# MainCon.net
KiCad netlist of a schematic drawn in Altium Designer
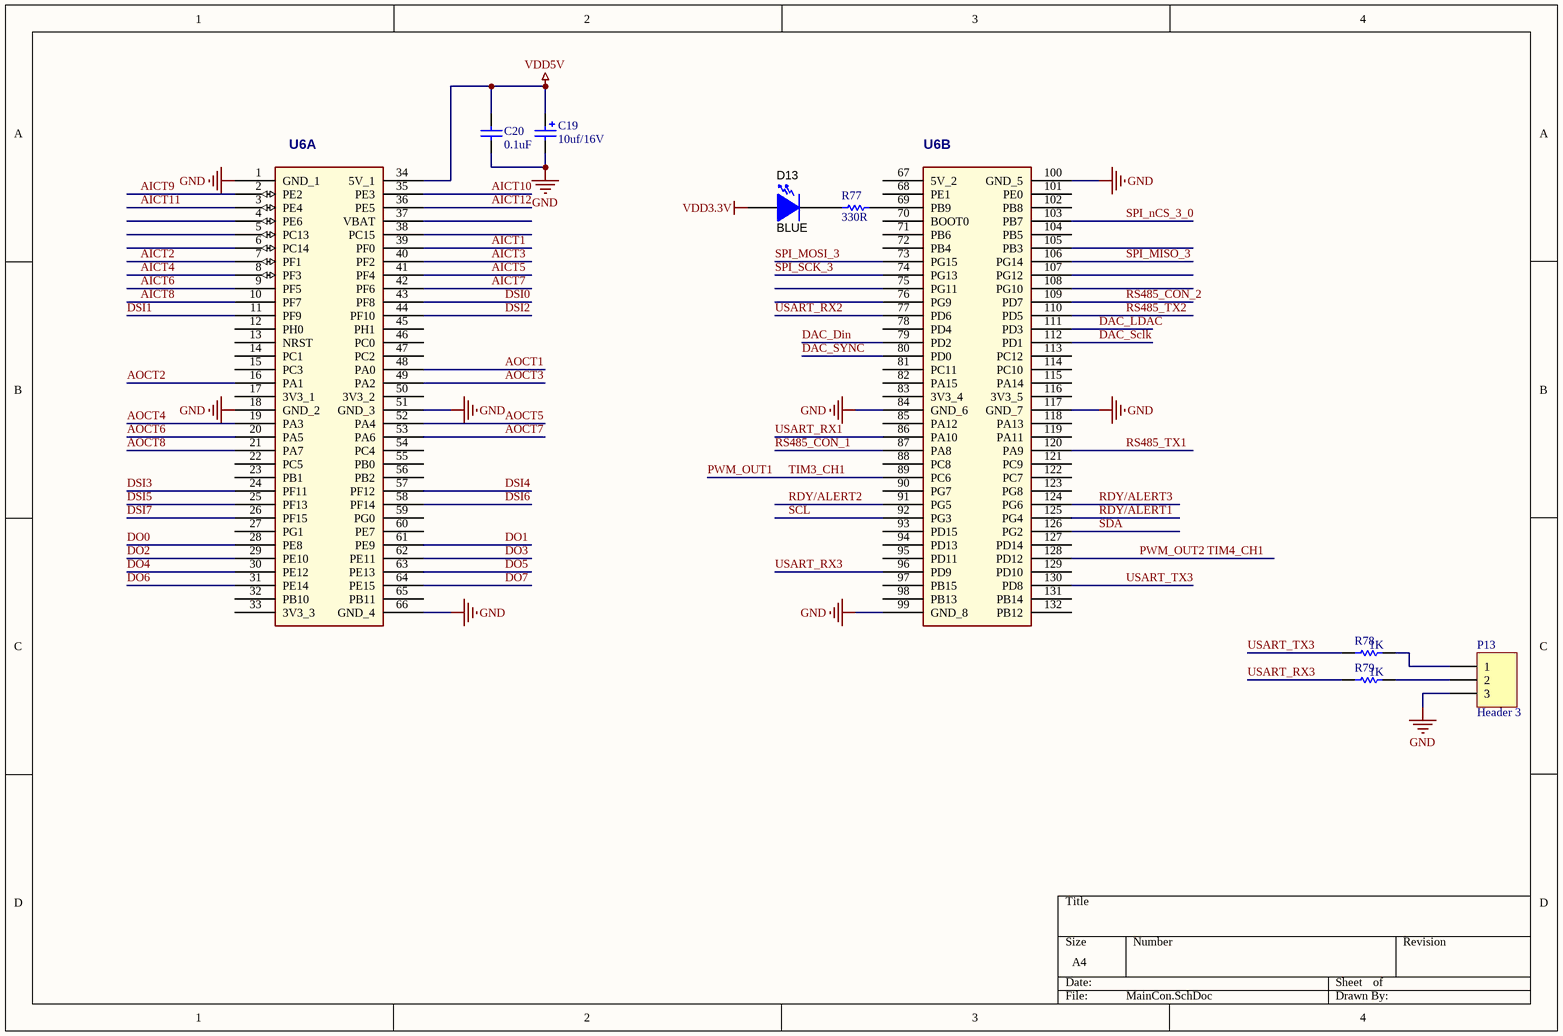
[diagram p0: MainCon.SchDoc]

(export (version "E")
  (design (tool "Eeschema 10.0.6"))
  (components
    (comp (ref "C19")
      (value "10uf/16V")
      (footprint "Cap-A")
      (description "Polarized Capacitor (Axial)")
      (fields (field (name "PUBLISHER") "Altium Limited"))
      (libsource (lib "Miscellaneous Devices") (part "Cap Pol2"))
    )
    (comp (ref "C20")
      (value "0.1uF")
      (footprint "C0805")
      (description "Capacitor")
      (fields (field (name "Comment") "Cap") (field (name "PUBLISHER") "Altium Limited"))
      (libsource (lib "main board") (part "Cap_2"))
    )
    (comp (ref "D13")
      (value "BLUE")
      (footprint "D0805")
      (description "LED, GREEN SMD")
      (fields
        (field (name "MANUFACTURER") "Rohm")
        (field (name "PARTNUMBER") "SML-P12YTT86")
        (field (name "PUBLISHER") "Texas Instruments")
      )
      (libsource (lib "REl") (part "SML-P12YTT86"))
    )
    (comp (ref "P13")
      (value "Header 3")
      (footprint "HDR1X3")
      (description "Header, 3-Pin")
      (fields (field (name "PUBLISHER") "Altium Limited"))
      (libsource (lib "Miscellaneous Connectors") (part "Header 3"))
    )
    (comp (ref "R77")
      (value "330R")
      (footprint "0805")
      (description "Semiconductor Resistor")
      (fields (field (name "Comment") "Res Semi") (field (name "PUBLISHER") "Altium Limited"))
      (libsource (lib "Miscellaneous Devices") (part "Res Semi"))
    )
    (comp (ref "R78")
      (value "1K")
      (footprint "0805")
      (description "Resistor")
      (fields (field (name "Comment") "Res1") (field (name "PUBLISHER") "Altium Limited"))
      (libsource (lib "Miscellaneous Devices") (part "Res1"))
    )
    (comp (ref "R79")
      (value "1K")
      (footprint "0805")
      (description "Resistor")
      (fields (field (name "Comment") "Res1") (field (name "PUBLISHER") "Altium Limited"))
      (libsource (lib "Miscellaneous Devices") (part "Res1"))
    )
    (comp (ref "U6") (value "STM32Z_MOD") (libsource (lib "*") (part "STM32Z_MOD")))
  )
  (nets
    (net (code "1") (name "/AICT1") (class "Default")
      (node (ref "U6") (pin "39") (pinfunction "PF0_39") (pintype "passive"))
    )
    (net (code "2") (name "/AICT2") (class "Default")
      (node (ref "U6") (pin "7") (pinfunction "PF1_7") (pintype "bidirectional"))
    )
    (net (code "3") (name "/AICT3") (class "Default")
      (node (ref "U6") (pin "40") (pinfunction "PF2_40") (pintype "passive"))
    )
    (net (code "4") (name "/AICT4") (class "Default")
      (node (ref "U6") (pin "8") (pinfunction "PF3_8") (pintype "bidirectional"))
    )
    (net (code "5") (name "/AICT5") (class "Default")
      (node (ref "U6") (pin "41") (pinfunction "PF4_41") (pintype "passive"))
    )
    (net (code "6") (name "/AICT6") (class "Default")
      (node (ref "U6") (pin "9") (pinfunction "PF5_9") (pintype "passive"))
    )
    (net (code "7") (name "/AICT7") (class "Default")
      (node (ref "U6") (pin "42") (pinfunction "PF6_42") (pintype "passive"))
    )
    (net (code "8") (name "/AICT8") (class "Default")
      (node (ref "U6") (pin "10") (pinfunction "PF7_10") (pintype "passive"))
    )
    (net (code "9") (name "/AICT9") (class "Default")
      (node (ref "U6") (pin "2") (pinfunction "PE2_2") (pintype "bidirectional"))
    )
    (net (code "10") (name "/AICT10") (class "Default")
      (node (ref "U6") (pin "35") (pinfunction "PE3_35") (pintype "passive"))
    )
    (net (code "11") (name "/AICT11") (class "Default")
      (node (ref "U6") (pin "3") (pinfunction "PE4_3") (pintype "bidirectional"))
    )
    (net (code "12") (name "/AICT12") (class "Default")
      (node (ref "U6") (pin "36") (pinfunction "PE5_36") (pintype "passive"))
    )
    (net (code "13") (name "/AOCT1") (class "Default")
      (node (ref "U6") (pin "48") (pinfunction "PA0_48") (pintype "passive"))
    )
    (net (code "14") (name "/AOCT2") (class "Default")
      (node (ref "U6") (pin "16") (pinfunction "PA1_16") (pintype "passive"))
    )
    (net (code "15") (name "/AOCT3") (class "Default")
      (node (ref "U6") (pin "49") (pinfunction "PA2_49") (pintype "passive"))
    )
    (net (code "16") (name "/AOCT4") (class "Default")
      (node (ref "U6") (pin "19") (pinfunction "PA3_19") (pintype "passive"))
    )
    (net (code "17") (name "/AOCT5") (class "Default")
      (node (ref "U6") (pin "52") (pinfunction "PA4_52") (pintype "passive"))
    )
    (net (code "18") (name "/AOCT6") (class "Default")
      (node (ref "U6") (pin "20") (pinfunction "PA5_20") (pintype "passive"))
    )
    (net (code "19") (name "/AOCT7") (class "Default")
      (node (ref "U6") (pin "53") (pinfunction "PA6_53") (pintype "passive"))
    )
    (net (code "20") (name "/AOCT8") (class "Default")
      (node (ref "U6") (pin "21") (pinfunction "PA7_21") (pintype "passive"))
    )
    (net (code "21") (name "/DAC_Din") (class "Default")
      (node (ref "U6") (pin "79") (pinfunction "PD2_79") (pintype "passive"))
    )
    (net (code "22") (name "/DAC_LDAC") (class "Default")
      (node (ref "U6") (pin "111") (pinfunction "PD3_111") (pintype "passive"))
    )
    (net (code "23") (name "/DAC_SYNC") (class "Default")
      (node (ref "U6") (pin "80") (pinfunction "PD0_80") (pintype "passive"))
    )
    (net (code "24") (name "/DAC_Sclk") (class "Default")
      (node (ref "U6") (pin "112") (pinfunction "PD1_112") (pintype "passive"))
    )
    (net (code "25") (name "/DO0") (class "Default")
      (node (ref "U6") (pin "28") (pinfunction "PE8_28") (pintype "passive"))
    )
    (net (code "26") (name "/DO1") (class "Default")
      (node (ref "U6") (pin "61") (pinfunction "PE9_61") (pintype "passive"))
    )
    (net (code "27") (name "/DO2") (class "Default")
      (node (ref "U6") (pin "29") (pinfunction "PE10_29") (pintype "passive"))
    )
    (net (code "28") (name "/DO3") (class "Default")
      (node (ref "U6") (pin "62") (pinfunction "PE11_62") (pintype "passive"))
    )
    (net (code "29") (name "/DO4") (class "Default")
      (node (ref "U6") (pin "30") (pinfunction "PE12_30") (pintype "passive"))
    )
    (net (code "30") (name "/DO5") (class "Default")
      (node (ref "U6") (pin "63") (pinfunction "PE13_63") (pintype "passive"))
    )
    (net (code "31") (name "/DO6") (class "Default")
      (node (ref "U6") (pin "31") (pinfunction "PE14_31") (pintype "passive"))
    )
    (net (code "32") (name "/DO7") (class "Default")
      (node (ref "U6") (pin "64") (pinfunction "PE15_64") (pintype "passive"))
    )
    (net (code "33") (name "/DSI0") (class "Default")
      (node (ref "U6") (pin "43") (pinfunction "PF8_43") (pintype "passive"))
    )
    (net (code "34") (name "/DSI1") (class "Default")
      (node (ref "U6") (pin "11") (pinfunction "PF9_11") (pintype "passive"))
    )
    (net (code "35") (name "/DSI2") (class "Default")
      (node (ref "U6") (pin "44") (pinfunction "PF10_44") (pintype "passive"))
    )
    (net (code "36") (name "/DSI3") (class "Default")
      (node (ref "U6") (pin "24") (pinfunction "PF11_24") (pintype "passive"))
    )
    (net (code "37") (name "/DSI4") (class "Default")
      (node (ref "U6") (pin "57") (pinfunction "PF12_57") (pintype "passive"))
    )
    (net (code "38") (name "/DSI5") (class "Default")
      (node (ref "U6") (pin "25") (pinfunction "PF13_25") (pintype "passive"))
    )
    (net (code "39") (name "/DSI6") (class "Default")
      (node (ref "U6") (pin "58") (pinfunction "PF14_58") (pintype "passive"))
    )
    (net (code "40") (name "/DSI7") (class "Default")
      (node (ref "U6") (pin "26") (pinfunction "PF15_26") (pintype "passive"))
    )
    (net (code "41") (name "/PWM_OUT1") (class "Default")
      (node (ref "U6") (pin "89") (pinfunction "PC6_89") (pintype "passive"))
    )
    (net (code "42") (name "/PWM_OUT2") (class "Default")
      (node (ref "U6") (pin "128") (pinfunction "PD12_128") (pintype "passive"))
    )
    (net (code "43") (name "/RDY{slash}ALERT1") (class "Default")
      (node (ref "U6") (pin "125") (pinfunction "PG4_125") (pintype "passive"))
    )
    (net (code "44") (name "/RDY{slash}ALERT2") (class "Default")
      (node (ref "U6") (pin "91") (pinfunction "PG5_91") (pintype "passive"))
    )
    (net (code "45") (name "/RDY{slash}ALERT3") (class "Default")
      (node (ref "U6") (pin "124") (pinfunction "PG6_124") (pintype "passive"))
    )
    (net (code "46") (name "/RS485_CON_1") (class "Default")
      (node (ref "U6") (pin "87") (pinfunction "PA8_87") (pintype "passive"))
    )
    (net (code "47") (name "/RS485_CON_2") (class "Default")
      (node (ref "U6") (pin "109") (pinfunction "PD7_109") (pintype "passive"))
    )
    (net (code "48") (name "/RS485_TX1") (class "Default")
      (node (ref "U6") (pin "120") (pinfunction "PA9_120") (pintype "passive"))
    )
    (net (code "49") (name "/RS485_TX2") (class "Default")
      (node (ref "U6") (pin "110") (pinfunction "PD5_110") (pintype "passive"))
    )
    (net (code "50") (name "/SCL") (class "Default")
      (node (ref "U6") (pin "92") (pinfunction "PG3_92") (pintype "passive"))
    )
    (net (code "51") (name "/SDA") (class "Default")
      (node (ref "U6") (pin "126") (pinfunction "PG2_126") (pintype "passive"))
    )
    (net (code "52") (name "/SPI_MISO_3") (class "Default")
      (node (ref "U6") (pin "106") (pinfunction "PG14_106") (pintype "passive"))
    )
    (net (code "53") (name "/SPI_MOSI_3") (class "Default")
      (node (ref "U6") (pin "73") (pinfunction "PG15_73") (pintype "passive"))
    )
    (net (code "54") (name "/SPI_SCK_3") (class "Default")
      (node (ref "U6") (pin "74") (pinfunction "PG13_74") (pintype "passive"))
    )
    (net (code "55") (name "/SPI_nCS_3_0") (class "Default")
      (node (ref "U6") (pin "103") (pinfunction "PB7_103") (pintype "passive"))
    )
    (net (code "56") (name "/USART_RX1") (class "Default")
      (node (ref "U6") (pin "86") (pinfunction "PA10_86") (pintype "passive"))
    )
    (net (code "57") (name "/USART_RX2") (class "Default")
      (node (ref "U6") (pin "77") (pinfunction "PD6_77") (pintype "passive"))
    )
    (net (code "58") (name "/USART_RX3") (class "Default")
      (node (ref "R79") (pin "1") (pinfunction "1_1") (pintype "passive"))
      (node (ref "U6") (pin "96") (pinfunction "PD9_96") (pintype "passive"))
    )
    (net (code "59") (name "/USART_TX3") (class "Default")
      (node (ref "R78") (pin "1") (pinfunction "1_1") (pintype "passive"))
      (node (ref "U6") (pin "130") (pinfunction "PD8_130") (pintype "passive"))
    )
    (net (code "60") (name "GND") (class "Default")
      (node (ref "C19") (pin "2") (pinfunction "2_2") (pintype "passive"))
      (node (ref "C20") (pin "1") (pinfunction "1_1") (pintype "passive"))
      (node (ref "P13") (pin "3") (pinfunction "3_3") (pintype "passive"))
      (node (ref "U6") (pin "1") (pinfunction "GND_1_1") (pintype "passive"))
      (node (ref "U6") (pin "100") (pinfunction "GND_5_100") (pintype "passive"))
      (node (ref "U6") (pin "117") (pinfunction "GND_7_117") (pintype "passive"))
      (node (ref "U6") (pin "18") (pinfunction "GND_2_18") (pintype "passive"))
      (node (ref "U6") (pin "51") (pinfunction "GND_3_51") (pintype "passive"))
      (node (ref "U6") (pin "66") (pinfunction "GND_4_66") (pintype "passive"))
      (node (ref "U6") (pin "84") (pinfunction "GND_6_84") (pintype "passive"))
      (node (ref "U6") (pin "99") (pinfunction "GND_8_99") (pintype "passive"))
    )
    (net (code "61") (name "Net-(D13-K)") (class "Default")
      (node (ref "D13") (pin "2") (pinfunction "K_2") (pintype "passive"))
      (node (ref "R77") (pin "2") (pinfunction "2_2") (pintype "passive"))
    )
    (net (code "62") (name "Net-(P13-Pad1)") (class "Default")
      (node (ref "P13") (pin "1") (pinfunction "1_1") (pintype "passive"))
      (node (ref "R78") (pin "2") (pinfunction "2_2") (pintype "passive"))
    )
    (net (code "63") (name "Net-(P13-Pad2)") (class "Default")
      (node (ref "P13") (pin "2") (pinfunction "2_2") (pintype "passive"))
      (node (ref "R79") (pin "2") (pinfunction "2_2") (pintype "passive"))
    )
    (net (code "64") (name "Net-(U6B-PB9)") (class "Default")
      (node (ref "R77") (pin "1") (pinfunction "1_1") (pintype "passive"))
      (node (ref "U6") (pin "69") (pinfunction "PB9_69") (pintype "passive"))
    )
    (net (code "65") (name "VDD3.3V") (class "Default")
      (node (ref "D13") (pin "1") (pinfunction "A_1") (pintype "passive"))
    )
    (net (code "66") (name "VDD5V") (class "Default")
      (node (ref "C19") (pin "1") (pinfunction "1_1") (pintype "passive"))
      (node (ref "C20") (pin "2") (pinfunction "2_2") (pintype "passive"))
      (node (ref "U6") (pin "34") (pinfunction "5V_1_34") (pintype "passive"))
    )
    (net (code "67") (name "unconnected-(U6A-3V3_1-Pad17)") (class "Default")
      (node (ref "U6") (pin "17") (pinfunction "3V3_1_17") (pintype "passive"))
    )
    (net (code "68") (name "unconnected-(U6A-3V3_2-Pad50)") (class "Default")
      (node (ref "U6") (pin "50") (pinfunction "3V3_2_50") (pintype "passive"))
    )
    (net (code "69") (name "unconnected-(U6A-3V3_3-Pad33)") (class "Default")
      (node (ref "U6") (pin "33") (pinfunction "3V3_3_33") (pintype "passive"))
    )
    (net (code "70") (name "unconnected-(U6A-NRST-Pad13)") (class "Default")
      (node (ref "U6") (pin "13") (pinfunction "NRST_13") (pintype "passive"))
    )
    (net (code "71") (name "unconnected-(U6A-PB0-Pad55)") (class "Default")
      (node (ref "U6") (pin "55") (pinfunction "PB0_55") (pintype "passive"))
    )
    (net (code "72") (name "unconnected-(U6A-PB1-Pad23)") (class "Default")
      (node (ref "U6") (pin "23") (pinfunction "PB1_23") (pintype "passive"))
    )
    (net (code "73") (name "unconnected-(U6A-PB2-Pad56)") (class "Default")
      (node (ref "U6") (pin "56") (pinfunction "PB2_56") (pintype "passive"))
    )
    (net (code "74") (name "unconnected-(U6A-PB10-Pad32)") (class "Default")
      (node (ref "U6") (pin "32") (pinfunction "PB10_32") (pintype "passive"))
    )
    (net (code "75") (name "unconnected-(U6A-PB11-Pad65)") (class "Default")
      (node (ref "U6") (pin "65") (pinfunction "PB11_65") (pintype "passive"))
    )
    (net (code "76") (name "unconnected-(U6A-PC0-Pad46)") (class "Default")
      (node (ref "U6") (pin "46") (pinfunction "PC0_46") (pintype "passive"))
    )
    (net (code "77") (name "unconnected-(U6A-PC1-Pad14)") (class "Default")
      (node (ref "U6") (pin "14") (pinfunction "PC1_14") (pintype "passive"))
    )
    (net (code "78") (name "unconnected-(U6A-PC2-Pad47)") (class "Default")
      (node (ref "U6") (pin "47") (pinfunction "PC2_47") (pintype "passive"))
    )
    (net (code "79") (name "unconnected-(U6A-PC3-Pad15)") (class "Default")
      (node (ref "U6") (pin "15") (pinfunction "PC3_15") (pintype "passive"))
    )
    (net (code "80") (name "unconnected-(U6A-PC4-Pad54)") (class "Default")
      (node (ref "U6") (pin "54") (pinfunction "PC4_54") (pintype "passive"))
    )
    (net (code "81") (name "unconnected-(U6A-PC5-Pad22)") (class "Default")
      (node (ref "U6") (pin "22") (pinfunction "PC5_22") (pintype "passive"))
    )
    (net (code "82") (name "unconnected-(U6A-PC13-Pad5)") (class "Default")
      (node (ref "U6") (pin "5") (pinfunction "PC13_5") (pintype "bidirectional"))
    )
    (net (code "83") (name "unconnected-(U6A-PC14-Pad6)") (class "Default")
      (node (ref "U6") (pin "6") (pinfunction "PC14_6") (pintype "bidirectional"))
    )
    (net (code "84") (name "unconnected-(U6A-PC15-Pad38)") (class "Default")
      (node (ref "U6") (pin "38") (pinfunction "PC15_38") (pintype "passive"))
    )
    (net (code "85") (name "unconnected-(U6A-PE6-Pad4)") (class "Default")
      (node (ref "U6") (pin "4") (pinfunction "PE6_4") (pintype "bidirectional"))
    )
    (net (code "86") (name "unconnected-(U6A-PE7-Pad60)") (class "Default")
      (node (ref "U6") (pin "60") (pinfunction "PE7_60") (pintype "passive"))
    )
    (net (code "87") (name "unconnected-(U6A-PG0-Pad59)") (class "Default")
      (node (ref "U6") (pin "59") (pinfunction "PG0_59") (pintype "passive"))
    )
    (net (code "88") (name "unconnected-(U6A-PG1-Pad27)") (class "Default")
      (node (ref "U6") (pin "27") (pinfunction "PG1_27") (pintype "passive"))
    )
    (net (code "89") (name "unconnected-(U6A-PH0-Pad12)") (class "Default")
      (node (ref "U6") (pin "12") (pinfunction "PH0_12") (pintype "passive"))
    )
    (net (code "90") (name "unconnected-(U6A-PH1-Pad45)") (class "Default")
      (node (ref "U6") (pin "45") (pinfunction "PH1_45") (pintype "passive"))
    )
    (net (code "91") (name "unconnected-(U6A-VBAT-Pad37)") (class "Default")
      (node (ref "U6") (pin "37") (pinfunction "VBAT_37") (pintype "passive"))
    )
    (net (code "92") (name "unconnected-(U6B-3V3_4-Pad83)") (class "Default")
      (node (ref "U6") (pin "83") (pinfunction "3V3_4_83") (pintype "passive"))
    )
    (net (code "93") (name "unconnected-(U6B-3V3_5-Pad116)") (class "Default")
      (node (ref "U6") (pin "116") (pinfunction "3V3_5_116") (pintype "passive"))
    )
    (net (code "94") (name "unconnected-(U6B-5V_2-Pad67)") (class "Default")
      (node (ref "U6") (pin "67") (pinfunction "5V_2_67") (pintype "passive"))
    )
    (net (code "95") (name "unconnected-(U6B-BOOT0-Pad70)") (class "Default")
      (node (ref "U6") (pin "70") (pinfunction "BOOT0_70") (pintype "passive"))
    )
    (net (code "96") (name "unconnected-(U6B-PA11-Pad119)") (class "Default")
      (node (ref "U6") (pin "119") (pinfunction "PA11_119") (pintype "passive"))
    )
    (net (code "97") (name "unconnected-(U6B-PA12-Pad85)") (class "Default")
      (node (ref "U6") (pin "85") (pinfunction "PA12_85") (pintype "passive"))
    )
    (net (code "98") (name "unconnected-(U6B-PA13-Pad118)") (class "Default")
      (node (ref "U6") (pin "118") (pinfunction "PA13_118") (pintype "passive"))
    )
    (net (code "99") (name "unconnected-(U6B-PA14-Pad115)") (class "Default")
      (node (ref "U6") (pin "115") (pinfunction "PA14_115") (pintype "passive"))
    )
    (net (code "100") (name "unconnected-(U6B-PA15-Pad82)") (class "Default")
      (node (ref "U6") (pin "82") (pinfunction "PA15_82") (pintype "passive"))
    )
    (net (code "101") (name "unconnected-(U6B-PB3-Pad105)") (class "Default")
      (node (ref "U6") (pin "105") (pinfunction "PB3_105") (pintype "passive"))
    )
    (net (code "102") (name "unconnected-(U6B-PB4-Pad72)") (class "Default")
      (node (ref "U6") (pin "72") (pinfunction "PB4_72") (pintype "passive"))
    )
    (net (code "103") (name "unconnected-(U6B-PB5-Pad104)") (class "Default")
      (node (ref "U6") (pin "104") (pinfunction "PB5_104") (pintype "passive"))
    )
    (net (code "104") (name "unconnected-(U6B-PB6-Pad71)") (class "Default")
      (node (ref "U6") (pin "71") (pinfunction "PB6_71") (pintype "passive"))
    )
    (net (code "105") (name "unconnected-(U6B-PB8-Pad102)") (class "Default")
      (node (ref "U6") (pin "102") (pinfunction "PB8_102") (pintype "passive"))
    )
    (net (code "106") (name "unconnected-(U6B-PB12-Pad132)") (class "Default")
      (node (ref "U6") (pin "132") (pinfunction "PB12_132") (pintype "passive"))
    )
    (net (code "107") (name "unconnected-(U6B-PB13-Pad98)") (class "Default")
      (node (ref "U6") (pin "98") (pinfunction "PB13_98") (pintype "passive"))
    )
    (net (code "108") (name "unconnected-(U6B-PB14-Pad131)") (class "Default")
      (node (ref "U6") (pin "131") (pinfunction "PB14_131") (pintype "passive"))
    )
    (net (code "109") (name "unconnected-(U6B-PB15-Pad97)") (class "Default")
      (node (ref "U6") (pin "97") (pinfunction "PB15_97") (pintype "passive"))
    )
    (net (code "110") (name "unconnected-(U6B-PC7-Pad122)") (class "Default")
      (node (ref "U6") (pin "122") (pinfunction "PC7_122") (pintype "passive"))
    )
    (net (code "111") (name "unconnected-(U6B-PC8-Pad88)") (class "Default")
      (node (ref "U6") (pin "88") (pinfunction "PC8_88") (pintype "passive"))
    )
    (net (code "112") (name "unconnected-(U6B-PC9-Pad121)") (class "Default")
      (node (ref "U6") (pin "121") (pinfunction "PC9_121") (pintype "passive"))
    )
    (net (code "113") (name "unconnected-(U6B-PC10-Pad114)") (class "Default")
      (node (ref "U6") (pin "114") (pinfunction "PC10_114") (pintype "passive"))
    )
    (net (code "114") (name "unconnected-(U6B-PC11-Pad81)") (class "Default")
      (node (ref "U6") (pin "81") (pinfunction "PC11_81") (pintype "passive"))
    )
    (net (code "115") (name "unconnected-(U6B-PC12-Pad113)") (class "Default")
      (node (ref "U6") (pin "113") (pinfunction "PC12_113") (pintype "passive"))
    )
    (net (code "116") (name "unconnected-(U6B-PD4-Pad78)") (class "Default")
      (node (ref "U6") (pin "78") (pinfunction "PD4_78") (pintype "passive"))
    )
    (net (code "117") (name "unconnected-(U6B-PD10-Pad129)") (class "Default")
      (node (ref "U6") (pin "129") (pinfunction "PD10_129") (pintype "passive"))
    )
    (net (code "118") (name "unconnected-(U6B-PD11-Pad95)") (class "Default")
      (node (ref "U6") (pin "95") (pinfunction "PD11_95") (pintype "passive"))
    )
    (net (code "119") (name "unconnected-(U6B-PD13-Pad94)") (class "Default")
      (node (ref "U6") (pin "94") (pinfunction "PD13_94") (pintype "passive"))
    )
    (net (code "120") (name "unconnected-(U6B-PD14-Pad127)") (class "Default")
      (node (ref "U6") (pin "127") (pinfunction "PD14_127") (pintype "passive"))
    )
    (net (code "121") (name "unconnected-(U6B-PD15-Pad93)") (class "Default")
      (node (ref "U6") (pin "93") (pinfunction "PD15_93") (pintype "passive"))
    )
    (net (code "122") (name "unconnected-(U6B-PE0-Pad101)") (class "Default")
      (node (ref "U6") (pin "101") (pinfunction "PE0_101") (pintype "passive"))
    )
    (net (code "123") (name "unconnected-(U6B-PE1-Pad68)") (class "Default")
      (node (ref "U6") (pin "68") (pinfunction "PE1_68") (pintype "passive"))
    )
    (net (code "124") (name "unconnected-(U6B-PG7-Pad90)") (class "Default")
      (node (ref "U6") (pin "90") (pinfunction "PG7_90") (pintype "passive"))
    )
    (net (code "125") (name "unconnected-(U6B-PG8-Pad123)") (class "Default")
      (node (ref "U6") (pin "123") (pinfunction "PG8_123") (pintype "passive"))
    )
    (net (code "126") (name "unconnected-(U6B-PG9-Pad76)") (class "Default")
      (node (ref "U6") (pin "76") (pinfunction "PG9_76") (pintype "passive"))
    )
    (net (code "127") (name "unconnected-(U6B-PG10-Pad108)") (class "Default")
      (node (ref "U6") (pin "108") (pinfunction "PG10_108") (pintype "passive"))
    )
    (net (code "128") (name "unconnected-(U6B-PG11-Pad75)") (class "Default")
      (node (ref "U6") (pin "75") (pinfunction "PG11_75") (pintype "passive"))
    )
    (net (code "129") (name "unconnected-(U6B-PG12-Pad107)") (class "Default")
      (node (ref "U6") (pin "107") (pinfunction "PG12_107") (pintype "passive"))
    )
  )
)
